# SCH_modular-power_2024-03-29.net
KiCad netlist of a schematic drawn in EasyEDA
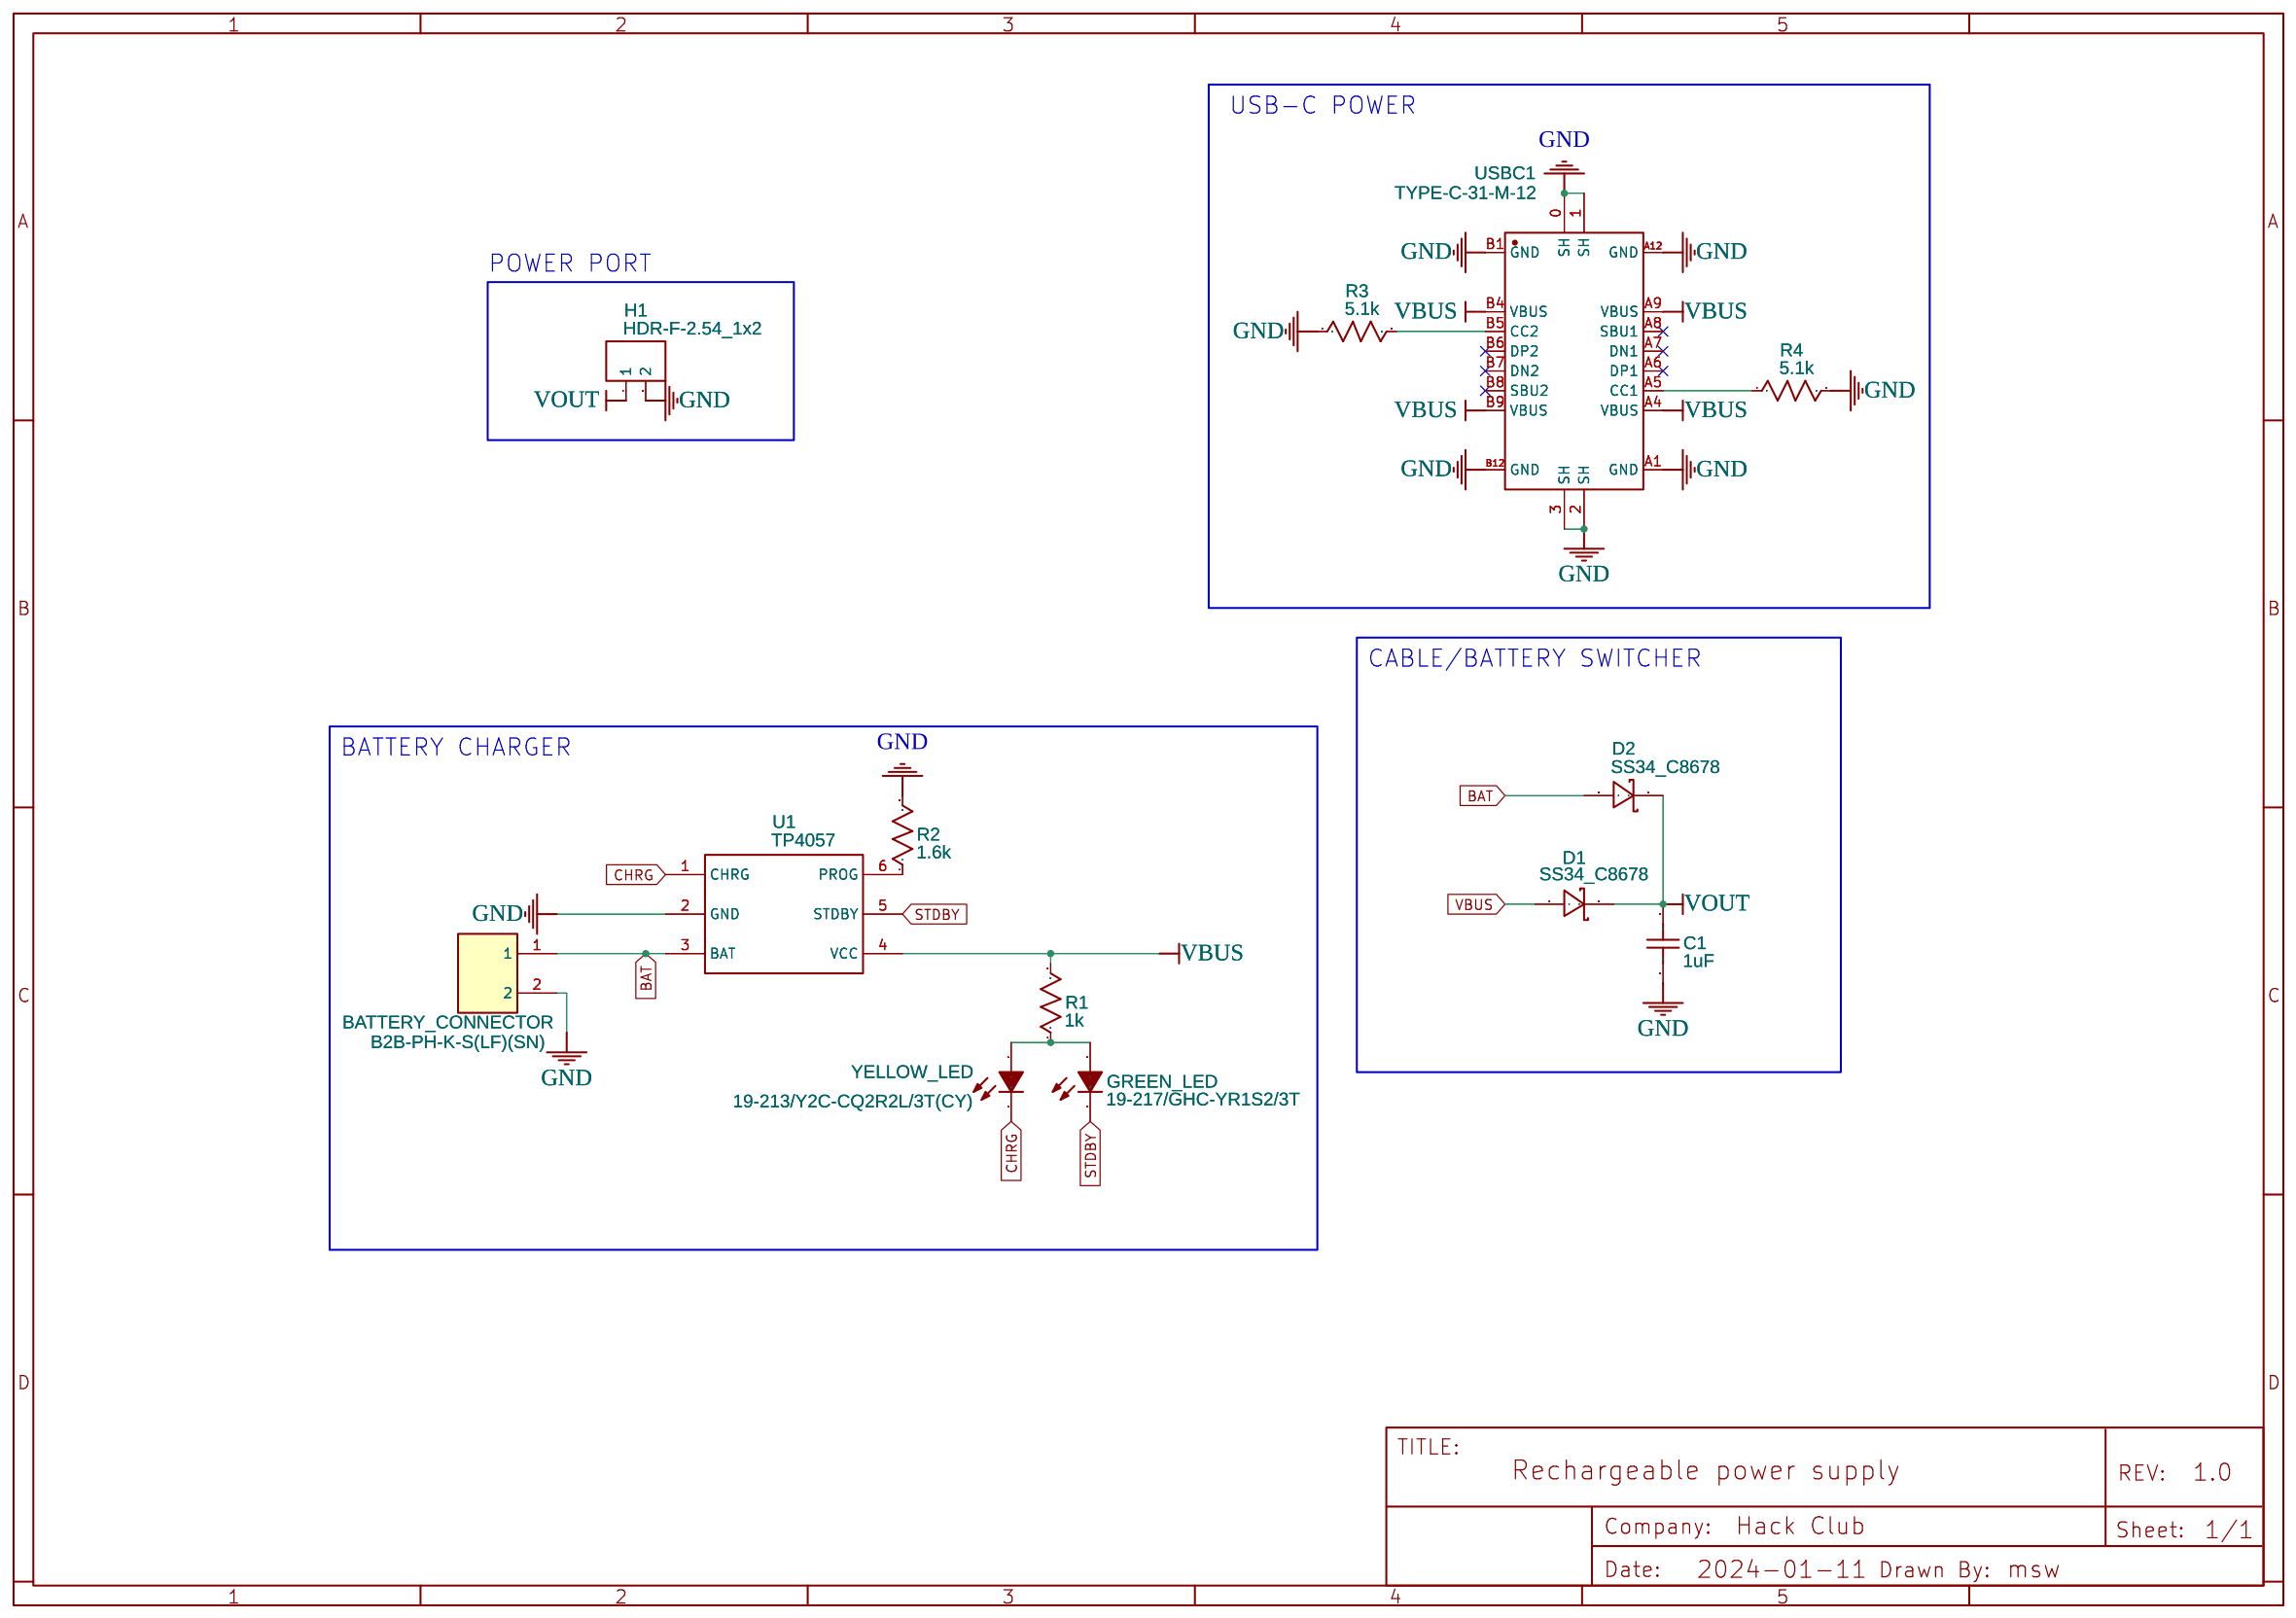
[diagram p0: schematic sheet]

(export (version "E")
  (design (tool "Eeschema 10.0.6"))
  (components
    (comp (ref "BATTERY_CONNECTOR")
      (value "B2B-PH-K-S(LF)(SN)")
      (fields (field (name "Manufacturer") "JST"))
      (libsource (lib "") (part "B2B-PH-K-S(LF)(SN)"))
    )
    (comp (ref "C1") (value "1uF") (libsource (lib "") (part "C_0603_US")))
    (comp (ref "D1")
      (value "SS34_C8678")
      (fields (field (name "Manufacturer Part") "SS34") (field (name "Manufacturer") "MDD"))
      (libsource (lib "") (part "SS34_C8678"))
    )
    (comp (ref "D2")
      (value "SS34_C8678")
      (fields (field (name "Manufacturer Part") "SS34") (field (name "Manufacturer") "MDD"))
      (libsource (lib "") (part "SS34_C8678"))
    )
    (comp (ref "GREEN_LED")
      (value "19-217/GHC-YR1S2/3T")
      (fields (field (name "Manufacturer") "EVERLIGHT(亿光)"))
      (libsource (lib "") (part "19-217/GHC-YR1S2/3T"))
    )
    (comp (ref "H1") (value "HDR-F-2.54_1x2") (libsource (lib "") (part "HDR-F-2.54_1x2")))
    (comp (ref "R1") (value "1k") (libsource (lib "") (part "R_0201_US")))
    (comp (ref "R2") (value "1.6k") (libsource (lib "") (part "R_0201_US")))
    (comp (ref "R3") (value "5.1k") (libsource (lib "") (part "R_0201_US_1")))
    (comp (ref "R4") (value "5.1k") (libsource (lib "") (part "R_0201_US_1")))
    (comp (ref "U1")
      (value "TP4057")
      (fields
        (field (name "Manufacturer Part") "TP4057-42-SOT26-R")
        (field (name "Manufacturer") "TOPPOWER(南京拓微)")
      )
      (libsource (lib "") (part "TP4057"))
    )
    (comp (ref "USBC1")
      (value "TYPE-C-31-M-12")
      (fields (field (name "Manufacturer") "韩国韩荣"))
      (libsource (lib "") (part "TYPE-C-31-M-12"))
    )
    (comp (ref "YELLOW_LED")
      (value "19-213/Y2C-CQ2R2L/3T(CY)")
      (fields (field (name "Manufacturer") "EVERLIGHT(亿光)"))
      (libsource (lib "") (part "19-213/Y2C-CQ2R2L/3T(CY)"))
    )
  )
  (nets
    (net (code "1") (name "BAT") (class "Default")
      (node (ref "BATTERY_CONNECTOR") (pin "1") (pinfunction "1_1") (pintype "input"))
      (node (ref "D2") (pin "2") (pinfunction "A_2") (pintype "unspecified"))
      (node (ref "U1") (pin "3") (pinfunction "BAT_3") (pintype "unspecified"))
    )
    (net (code "2") (name "CHRG") (class "Default")
      (node (ref "U1") (pin "1") (pinfunction "CHRG_1") (pintype "unspecified"))
      (node (ref "YELLOW_LED") (pin "1") (pinfunction "C_1") (pintype "input"))
    )
    (net (code "3") (name "GND") (class "Default")
      (node (ref "BATTERY_CONNECTOR") (pin "2") (pinfunction "2_2") (pintype "input"))
      (node (ref "C1") (pin "1") (pinfunction "1_1") (pintype "unspecified"))
      (node (ref "H1") (pin "2") (pinfunction "2_2") (pintype "input"))
      (node (ref "R2") (pin "2") (pinfunction "2_2") (pintype "unspecified"))
      (node (ref "R3") (pin "1") (pinfunction "1_1") (pintype "unspecified"))
      (node (ref "R4") (pin "2") (pinfunction "2_2") (pintype "unspecified"))
      (node (ref "U1") (pin "2") (pinfunction "GND_2") (pintype "unspecified"))
      (node (ref "USBC1") (pin "0") (pinfunction "SH_0") (pintype "unspecified"))
      (node (ref "USBC1") (pin "1") (pinfunction "SH_1") (pintype "unspecified"))
      (node (ref "USBC1") (pin "2") (pinfunction "SH_2") (pintype "unspecified"))
      (node (ref "USBC1") (pin "3") (pinfunction "SH_3") (pintype "unspecified"))
      (node (ref "USBC1") (pin "A1") (pinfunction "GND_A1") (pintype "unspecified"))
      (node (ref "USBC1") (pin "A12") (pinfunction "GND_A12") (pintype "unspecified"))
      (node (ref "USBC1") (pin "B1") (pinfunction "GND_B1") (pintype "unspecified"))
      (node (ref "USBC1") (pin "B12") (pinfunction "GND_B12") (pintype "unspecified"))
    )
    (net (code "4") (name "Net-(GREEN_LED-A)") (class "Default")
      (node (ref "GREEN_LED") (pin "2") (pinfunction "A_2") (pintype "input"))
      (node (ref "R1") (pin "1") (pinfunction "1_1") (pintype "unspecified"))
      (node (ref "YELLOW_LED") (pin "2") (pinfunction "A_2") (pintype "input"))
    )
    (net (code "5") (name "Net-(U1-PROG)") (class "Default")
      (node (ref "R2") (pin "1") (pinfunction "1_1") (pintype "unspecified"))
      (node (ref "U1") (pin "6") (pinfunction "PROG_6") (pintype "unspecified"))
    )
    (net (code "6") (name "Net-(USBC1-CC1)") (class "Default")
      (node (ref "R4") (pin "1") (pinfunction "1_1") (pintype "unspecified"))
      (node (ref "USBC1") (pin "A5") (pinfunction "CC1_A5") (pintype "unspecified"))
    )
    (net (code "7") (name "Net-(USBC1-CC2)") (class "Default")
      (node (ref "R3") (pin "2") (pinfunction "2_2") (pintype "unspecified"))
      (node (ref "USBC1") (pin "B5") (pinfunction "CC2_B5") (pintype "unspecified"))
    )
    (net (code "8") (name "STDBY") (class "Default")
      (node (ref "GREEN_LED") (pin "1") (pinfunction "C_1") (pintype "input"))
      (node (ref "U1") (pin "5") (pinfunction "STDBY_5") (pintype "unspecified"))
    )
    (net (code "9") (name "VBUS") (class "Default")
      (node (ref "D1") (pin "2") (pinfunction "A_2") (pintype "unspecified"))
      (node (ref "R1") (pin "2") (pinfunction "2_2") (pintype "unspecified"))
      (node (ref "U1") (pin "4") (pinfunction "VCC_4") (pintype "unspecified"))
      (node (ref "USBC1") (pin "A4") (pinfunction "VBUS_A4") (pintype "unspecified"))
      (node (ref "USBC1") (pin "A9") (pinfunction "VBUS_A9") (pintype "unspecified"))
      (node (ref "USBC1") (pin "B4") (pinfunction "VBUS_B4") (pintype "unspecified"))
      (node (ref "USBC1") (pin "B9") (pinfunction "VBUS_B9") (pintype "unspecified"))
    )
    (net (code "10") (name "VOUT") (class "Default")
      (node (ref "C1") (pin "2") (pinfunction "2_2") (pintype "unspecified"))
      (node (ref "D1") (pin "1") (pinfunction "K_1") (pintype "unspecified"))
      (node (ref "D2") (pin "1") (pinfunction "K_1") (pintype "unspecified"))
      (node (ref "H1") (pin "1") (pinfunction "1_1") (pintype "input"))
    )
    (net (code "11") (name "unconnected-(USBC1-DN1-PadA7)") (class "Default")
      (node (ref "USBC1") (pin "A7") (pinfunction "DN1_A7") (pintype "unspecified+no_connect"))
    )
    (net (code "12") (name "unconnected-(USBC1-DN2-PadB7)") (class "Default")
      (node (ref "USBC1") (pin "B7") (pinfunction "DN2_B7") (pintype "unspecified+no_connect"))
    )
    (net (code "13") (name "unconnected-(USBC1-DP1-PadA6)") (class "Default")
      (node (ref "USBC1") (pin "A6") (pinfunction "DP1_A6") (pintype "unspecified+no_connect"))
    )
    (net (code "14") (name "unconnected-(USBC1-DP2-PadB6)") (class "Default")
      (node (ref "USBC1") (pin "B6") (pinfunction "DP2_B6") (pintype "unspecified+no_connect"))
    )
    (net (code "15") (name "unconnected-(USBC1-SBU1-PadA8)") (class "Default")
      (node (ref "USBC1") (pin "A8") (pinfunction "SBU1_A8") (pintype "unspecified+no_connect"))
    )
    (net (code "16") (name "unconnected-(USBC1-SBU2-PadB8)") (class "Default")
      (node (ref "USBC1") (pin "B8") (pinfunction "SBU2_B8") (pintype "unspecified+no_connect"))
    )
  )
)
